# schemat.net
KiCad netlist of a schematic drawn in EAGLE
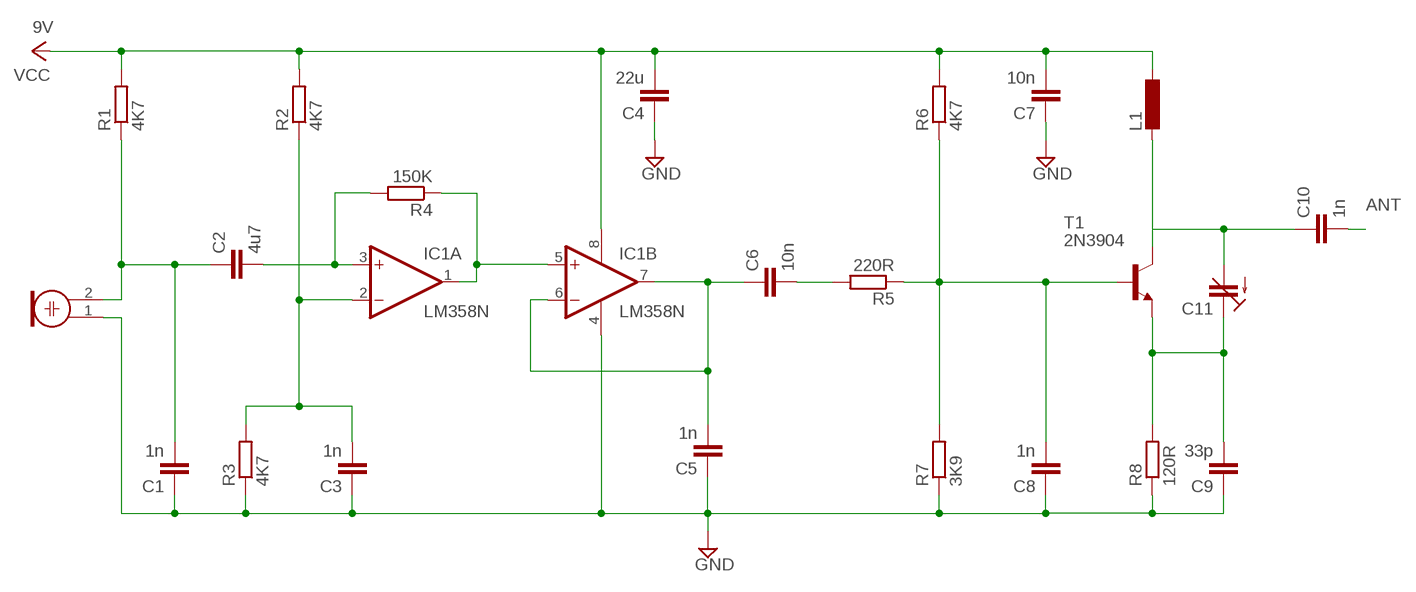
[diagram p0: schematic, sheet 1]

(export (version "E")
  (design (tool "Eeschema 10.0.6"))
  (components
    (comp (ref "C1")
      (value "1n")
      (footprint "eagle-import:C025-025X050")
      (libsource (lib "eagle-import") (part "C-EU025-025X050"))
    )
    (comp (ref "C2")
      (value "4u7")
      (footprint "eagle-import:C025-025X050")
      (libsource (lib "eagle-import") (part "C-EU025-025X050"))
    )
    (comp (ref "C3")
      (value "1n")
      (footprint "eagle-import:C025-025X050")
      (libsource (lib "eagle-import") (part "C-EU025-025X050"))
    )
    (comp (ref "C4")
      (value "22u")
      (footprint "eagle-import:C025-025X050")
      (libsource (lib "eagle-import") (part "C-EU025-025X050"))
    )
    (comp (ref "C5")
      (value "1n")
      (footprint "eagle-import:C025-025X050")
      (libsource (lib "eagle-import") (part "C-EU025-025X050"))
    )
    (comp (ref "C6")
      (value "10n")
      (footprint "eagle-import:C025-025X050")
      (libsource (lib "eagle-import") (part "C-EU025-025X050"))
    )
    (comp (ref "C7")
      (value "10n")
      (footprint "eagle-import:C025-025X050")
      (libsource (lib "eagle-import") (part "C-EU025-025X050"))
    )
    (comp (ref "C8")
      (value "1n")
      (footprint "eagle-import:C025-025X050")
      (libsource (lib "eagle-import") (part "C-EU025-025X050"))
    )
    (comp (ref "C9")
      (value "33p")
      (footprint "eagle-import:C025-025X050")
      (libsource (lib "eagle-import") (part "C-EU025-025X050"))
    )
    (comp (ref "C10")
      (value "1n")
      (footprint "eagle-import:C025-025X050")
      (libsource (lib "eagle-import") (part "C-EU025-025X050"))
    )
    (comp (ref "C11")
      (value "C-TRIMM3040.428")
      (footprint "eagle-import:CTRIM3040.428")
      (libsource (lib "eagle-import") (part "C-TRIMM3040.428"))
    )
    (comp (ref "IC1")
      (value "LM358N")
      (footprint "eagle-import:DIL08")
      (libsource (lib "eagle-import") (part "LM358N"))
    )
    (comp (ref "L1")
      (value "L-EU0207/15")
      (footprint "eagle-import:0207_15")
      (libsource (lib "eagle-import") (part "L-EU0207/15"))
    )
    (comp (ref "M1")
      (value "ELECTRET_MICROPHON-F6050AP")
      (footprint "eagle-import:F6050AP")
      (libsource (lib "eagle-import") (part "ELECTRET_MICROPHON-F6050AP"))
    )
    (comp (ref "R1")
      (value "4K7")
      (footprint "eagle-import:0204_7")
      (libsource (lib "eagle-import") (part "R-EU_0204/7"))
    )
    (comp (ref "R2")
      (value "4K7")
      (footprint "eagle-import:0204_7")
      (libsource (lib "eagle-import") (part "R-EU_0204/7"))
    )
    (comp (ref "R3")
      (value "4K7")
      (footprint "eagle-import:0204_7")
      (libsource (lib "eagle-import") (part "R-EU_0204/7"))
    )
    (comp (ref "R4")
      (value "150K")
      (footprint "eagle-import:0204_7")
      (libsource (lib "eagle-import") (part "R-EU_0204/7"))
    )
    (comp (ref "R5")
      (value "220R")
      (footprint "eagle-import:0204_7")
      (libsource (lib "eagle-import") (part "R-EU_0204/7"))
    )
    (comp (ref "R6")
      (value "4K7")
      (footprint "eagle-import:0204_7")
      (libsource (lib "eagle-import") (part "R-EU_0204/7"))
    )
    (comp (ref "R7")
      (value "3K9")
      (footprint "eagle-import:0204_7")
      (libsource (lib "eagle-import") (part "R-EU_0204/7"))
    )
    (comp (ref "R8")
      (value "120R")
      (footprint "eagle-import:0204_7")
      (libsource (lib "eagle-import") (part "R-EU_0204/7"))
    )
    (comp (ref "T1")
      (value "2N3904")
      (footprint "eagle-import:TO92")
      (libsource (lib "eagle-import") (part "2N3904"))
    )
  )
  (nets
    (net (code "1") (name "/ANT") (class "Default")
      (node (ref "C10") (pin "2") (pinfunction "2_2") (pintype "passive"))
    )
    (net (code "2") (name "GND") (class "Default")
      (node (ref "C1") (pin "1") (pinfunction "1_1") (pintype "passive"))
      (node (ref "C3") (pin "1") (pinfunction "1_1") (pintype "passive"))
      (node (ref "C4") (pin "1") (pinfunction "1_1") (pintype "passive"))
      (node (ref "C5") (pin "1") (pinfunction "1_1") (pintype "passive"))
      (node (ref "C7") (pin "1") (pinfunction "1_1") (pintype "passive"))
      (node (ref "C8") (pin "1") (pinfunction "1_1") (pintype "passive"))
      (node (ref "C9") (pin "1") (pinfunction "1_1") (pintype "passive"))
      (node (ref "IC1") (pin "4") (pinfunction "V-_4") (pintype "power_in"))
      (node (ref "M1") (pin "1") (pinfunction "1_1") (pintype "passive"))
      (node (ref "R3") (pin "1") (pinfunction "1_1") (pintype "passive"))
      (node (ref "R7") (pin "1") (pinfunction "1_1") (pintype "passive"))
      (node (ref "R8") (pin "1") (pinfunction "1_1") (pintype "passive"))
    )
    (net (code "3") (name "Net-(C1-Pad2)") (class "Default")
      (node (ref "C1") (pin "2") (pinfunction "2_2") (pintype "passive"))
      (node (ref "C2") (pin "1") (pinfunction "1_1") (pintype "passive"))
      (node (ref "M1") (pin "2") (pinfunction "2_2") (pintype "passive"))
      (node (ref "R1") (pin "1") (pinfunction "1_1") (pintype "passive"))
    )
    (net (code "4") (name "Net-(C6-Pad2)") (class "Default")
      (node (ref "C6") (pin "2") (pinfunction "2_2") (pintype "passive"))
      (node (ref "R5") (pin "2") (pinfunction "2_2") (pintype "passive"))
    )
    (net (code "5") (name "Net-(C11-A)") (class "Default")
      (node (ref "C10") (pin "1") (pinfunction "1_1") (pintype "passive"))
      (node (ref "C11") (pin "2") (pinfunction "A_2") (pintype "passive"))
      (node (ref "L1") (pin "2") (pinfunction "2_2") (pintype "passive"))
      (node (ref "T1") (pin "1") (pinfunction "C_1") (pintype "passive"))
    )
    (net (code "6") (name "Net-(C11-E)") (class "Default")
      (node (ref "C11") (pin "1A") (pinfunction "E_1A") (pintype "passive"))
      (node (ref "C9") (pin "2") (pinfunction "2_2") (pintype "passive"))
      (node (ref "R8") (pin "2") (pinfunction "2_2") (pintype "passive"))
      (node (ref "T1") (pin "3") (pinfunction "E_3") (pintype "passive"))
    )
    (net (code "7") (name "Net-(IC1A-+IN)") (class "Default")
      (node (ref "C2") (pin "2") (pinfunction "2_2") (pintype "passive"))
      (node (ref "IC1") (pin "3") (pinfunction "+IN_3") (pintype "input"))
      (node (ref "R4") (pin "2") (pinfunction "2_2") (pintype "passive"))
    )
    (net (code "8") (name "Net-(IC1A--IN)") (class "Default")
      (node (ref "C3") (pin "2") (pinfunction "2_2") (pintype "passive"))
      (node (ref "IC1") (pin "2") (pinfunction "-IN_2") (pintype "input"))
      (node (ref "R2") (pin "1") (pinfunction "1_1") (pintype "passive"))
      (node (ref "R3") (pin "2") (pinfunction "2_2") (pintype "passive"))
    )
    (net (code "9") (name "Net-(IC1A-OUT)") (class "Default")
      (node (ref "IC1") (pin "1") (pinfunction "OUT_1") (pintype "output"))
      (node (ref "IC1") (pin "5") (pinfunction "+IN_5") (pintype "input"))
      (node (ref "R4") (pin "1") (pinfunction "1_1") (pintype "passive"))
    )
    (net (code "10") (name "Net-(IC1B--IN)") (class "Default")
      (node (ref "C5") (pin "2") (pinfunction "2_2") (pintype "passive"))
      (node (ref "C6") (pin "1") (pinfunction "1_1") (pintype "passive"))
      (node (ref "IC1") (pin "6") (pinfunction "-IN_6") (pintype "input"))
      (node (ref "IC1") (pin "7") (pinfunction "OUT_7") (pintype "output"))
    )
    (net (code "11") (name "Net-(T1-B)") (class "Default")
      (node (ref "C8") (pin "2") (pinfunction "2_2") (pintype "passive"))
      (node (ref "R5") (pin "1") (pinfunction "1_1") (pintype "passive"))
      (node (ref "R6") (pin "1") (pinfunction "1_1") (pintype "passive"))
      (node (ref "R7") (pin "2") (pinfunction "2_2") (pintype "passive"))
      (node (ref "T1") (pin "2") (pinfunction "B_2") (pintype "passive"))
    )
    (net (code "12") (name "VCC") (class "Default")
      (node (ref "C4") (pin "2") (pinfunction "2_2") (pintype "passive"))
      (node (ref "C7") (pin "2") (pinfunction "2_2") (pintype "passive"))
      (node (ref "IC1") (pin "8") (pinfunction "V+_8") (pintype "power_in"))
      (node (ref "L1") (pin "1") (pinfunction "1_1") (pintype "passive"))
      (node (ref "R1") (pin "2") (pinfunction "2_2") (pintype "passive"))
      (node (ref "R2") (pin "2") (pinfunction "2_2") (pintype "passive"))
      (node (ref "R6") (pin "2") (pinfunction "2_2") (pintype "passive"))
    )
  )
)
